# EM4095_base_circuit_w_series.net
KiCad netlist of a schematic drawn in EAGLE
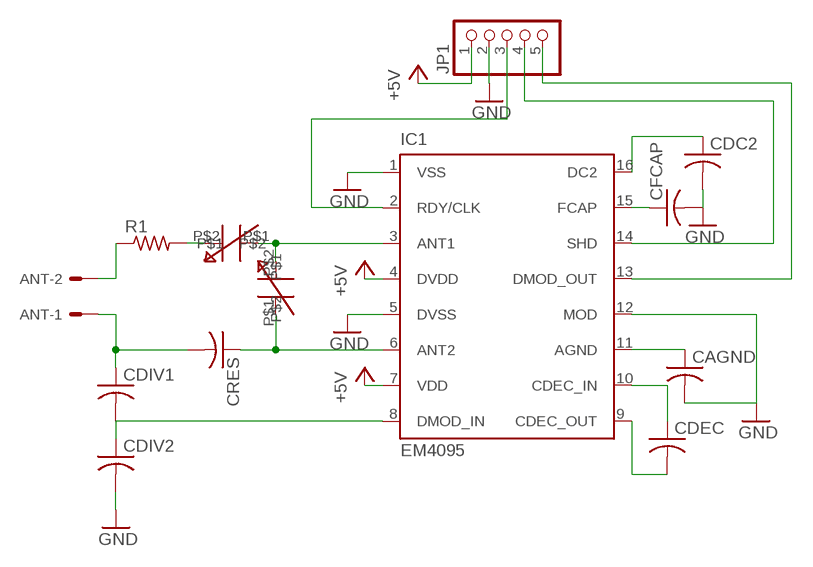
[diagram p0: schematic, sheet 1]

(export (version "E")
  (design (tool "Eeschema 10.0.6"))
  (components
    (comp (ref "ANT")
      (value "KK-156-2")
      (footprint "eagle-import:KK-156-2")
      (libsource (lib "eagle-import") (part "KK-156-2"))
    )
    (comp (ref "CAGND")
      (value "C-USC1206K")
      (footprint "eagle-import:C1206K")
      (libsource (lib "eagle-import") (part "C-USC1206K"))
    )
    (comp (ref "CDC2")
      (value "C-USC1206K")
      (footprint "eagle-import:C1206K")
      (libsource (lib "eagle-import") (part "C-USC1206K"))
    )
    (comp (ref "CDEC")
      (value "C-USC1206K")
      (footprint "eagle-import:C1206K")
      (libsource (lib "eagle-import") (part "C-USC1206K"))
    )
    (comp (ref "CDIV1")
      (value "C-USC1206K")
      (footprint "eagle-import:C1206K")
      (libsource (lib "eagle-import") (part "C-USC1206K"))
    )
    (comp (ref "CDIV2")
      (value "C-USC1206K")
      (footprint "eagle-import:C1206K")
      (libsource (lib "eagle-import") (part "C-USC1206K"))
    )
    (comp (ref "CFCAP")
      (value "C-USC1206K")
      (footprint "eagle-import:C1206K")
      (libsource (lib "eagle-import") (part "C-USC1206K"))
    )
    (comp (ref "CRES")
      (value "C-USC1206K")
      (footprint "eagle-import:C1206K")
      (libsource (lib "eagle-import") (part "C-USC1206K"))
    )
    (comp (ref "IC1")
      (value "EM4095")
      (footprint "eagle-import:SO16")
      (libsource (lib "eagle-import") (part "EM4095"))
    )
    (comp (ref "JP1")
      (value "PINHD-1X5")
      (footprint "eagle-import:1X05")
      (libsource (lib "eagle-import") (part "PINHD-1X5"))
    )
    (comp (ref "R1")
      (value "R-US_R1206")
      (footprint "eagle-import:R1206")
      (libsource (lib "eagle-import") (part "R-US_R1206"))
    )
    (comp (ref "U$1")
      (value "TZB4Z100AB10R00")
      (footprint "eagle-import:TZB4Z100AB10R00")
      (libsource (lib "eagle-import") (part "TZB4Z100AB10R00"))
    )
    (comp (ref "U$2")
      (value "TZB4Z100AB10R00")
      (footprint "eagle-import:TZB4Z100AB10R00")
      (libsource (lib "eagle-import") (part "TZB4Z100AB10R00"))
    )
  )
  (nets
    (net (code "1") (name "+5V") (class "Default")
      (node (ref "IC1") (pin "4") (pinfunction "DVDD_4") (pintype "power_in"))
      (node (ref "IC1") (pin "7") (pinfunction "VDD_7") (pintype "power_in"))
      (node (ref "JP1") (pin "1") (pinfunction "1_1") (pintype "passive"))
    )
    (net (code "2") (name "GND") (class "Default")
      (node (ref "CAGND") (pin "2") (pinfunction "2_2") (pintype "passive"))
      (node (ref "CDC2") (pin "2") (pinfunction "2_2") (pintype "passive"))
      (node (ref "CDIV2") (pin "2") (pinfunction "2_2") (pintype "passive"))
      (node (ref "CFCAP") (pin "2") (pinfunction "2_2") (pintype "passive"))
      (node (ref "IC1") (pin "1") (pinfunction "VSS_1") (pintype "power_in"))
      (node (ref "IC1") (pin "12") (pinfunction "MOD_12") (pintype "input"))
      (node (ref "IC1") (pin "5") (pinfunction "DVSS_5") (pintype "power_in"))
      (node (ref "JP1") (pin "2") (pinfunction "2_2") (pintype "passive"))
    )
    (net (code "3") (name "Net-(ANTA-S)") (class "Default")
      (node (ref "ANT") (pin "1") (pinfunction "S_1") (pintype "passive"))
      (node (ref "CDIV1") (pin "1") (pinfunction "1_1") (pintype "passive"))
      (node (ref "CRES") (pin "2") (pinfunction "2_2") (pintype "passive"))
    )
    (net (code "4") (name "Net-(ANTB-S)") (class "Default")
      (node (ref "ANT") (pin "2") (pinfunction "S_2") (pintype "passive"))
      (node (ref "R1") (pin "1") (pinfunction "1_1") (pintype "passive"))
    )
    (net (code "5") (name "Net-(IC1-AGND)") (class "Default")
      (node (ref "CAGND") (pin "1") (pinfunction "1_1") (pintype "passive"))
      (node (ref "IC1") (pin "11") (pinfunction "AGND_11") (pintype "power_in"))
    )
    (net (code "6") (name "Net-(IC1-ANT1)") (class "Default")
      (node (ref "IC1") (pin "3") (pinfunction "ANT1_3") (pintype "passive"))
      (node (ref "U$1") (pin "P$2") (pinfunction "P$2_P$2") (pintype "bidirectional"))
      (node (ref "U$2") (pin "P$1") (pinfunction "P$1_P$1") (pintype "bidirectional"))
    )
    (net (code "7") (name "Net-(IC1-ANT2)") (class "Default")
      (node (ref "CRES") (pin "1") (pinfunction "1_1") (pintype "passive"))
      (node (ref "IC1") (pin "6") (pinfunction "ANT2_6") (pintype "passive"))
      (node (ref "U$1") (pin "P$1") (pinfunction "P$1_P$1") (pintype "bidirectional"))
    )
    (net (code "8") (name "Net-(IC1-CDEC_IN)") (class "Default")
      (node (ref "CDEC") (pin "1") (pinfunction "1_1") (pintype "passive"))
      (node (ref "IC1") (pin "10") (pinfunction "CDEC_IN_10") (pintype "input"))
    )
    (net (code "9") (name "Net-(IC1-CDEC_OUT)") (class "Default")
      (node (ref "CDEC") (pin "2") (pinfunction "2_2") (pintype "passive"))
      (node (ref "IC1") (pin "9") (pinfunction "CDEC_OUT_9") (pintype "output"))
    )
    (net (code "10") (name "Net-(IC1-DC2)") (class "Default")
      (node (ref "CDC2") (pin "1") (pinfunction "1_1") (pintype "passive"))
      (node (ref "IC1") (pin "16") (pinfunction "DC2_16") (pintype "passive"))
    )
    (net (code "11") (name "Net-(IC1-DMOD_IN)") (class "Default")
      (node (ref "CDIV1") (pin "2") (pinfunction "2_2") (pintype "passive"))
      (node (ref "CDIV2") (pin "1") (pinfunction "1_1") (pintype "passive"))
      (node (ref "IC1") (pin "8") (pinfunction "DMOD_IN_8") (pintype "input"))
    )
    (net (code "12") (name "Net-(IC1-DMOD_OUT)") (class "Default")
      (node (ref "IC1") (pin "13") (pinfunction "DMOD_OUT_13") (pintype "output"))
      (node (ref "JP1") (pin "5") (pinfunction "5_5") (pintype "passive"))
    )
    (net (code "13") (name "Net-(IC1-FCAP)") (class "Default")
      (node (ref "CFCAP") (pin "1") (pinfunction "1_1") (pintype "passive"))
      (node (ref "IC1") (pin "15") (pinfunction "FCAP_15") (pintype "passive"))
    )
    (net (code "14") (name "Net-(IC1-RDY{slash}CLK)") (class "Default")
      (node (ref "IC1") (pin "2") (pinfunction "RDY/CLK_2") (pintype "output"))
      (node (ref "JP1") (pin "3") (pinfunction "3_3") (pintype "passive"))
    )
    (net (code "15") (name "Net-(IC1-SHD)") (class "Default")
      (node (ref "IC1") (pin "14") (pinfunction "SHD_14") (pintype "input"))
      (node (ref "JP1") (pin "4") (pinfunction "4_4") (pintype "passive"))
    )
    (net (code "16") (name "Net-(R1-Pad2)") (class "Default")
      (node (ref "R1") (pin "2") (pinfunction "2_2") (pintype "passive"))
      (node (ref "U$2") (pin "P$2") (pinfunction "P$2_P$2") (pintype "bidirectional"))
    )
  )
)
